# FPGA_NonIO.net
KiCad netlist of a schematic drawn in Altium Designer
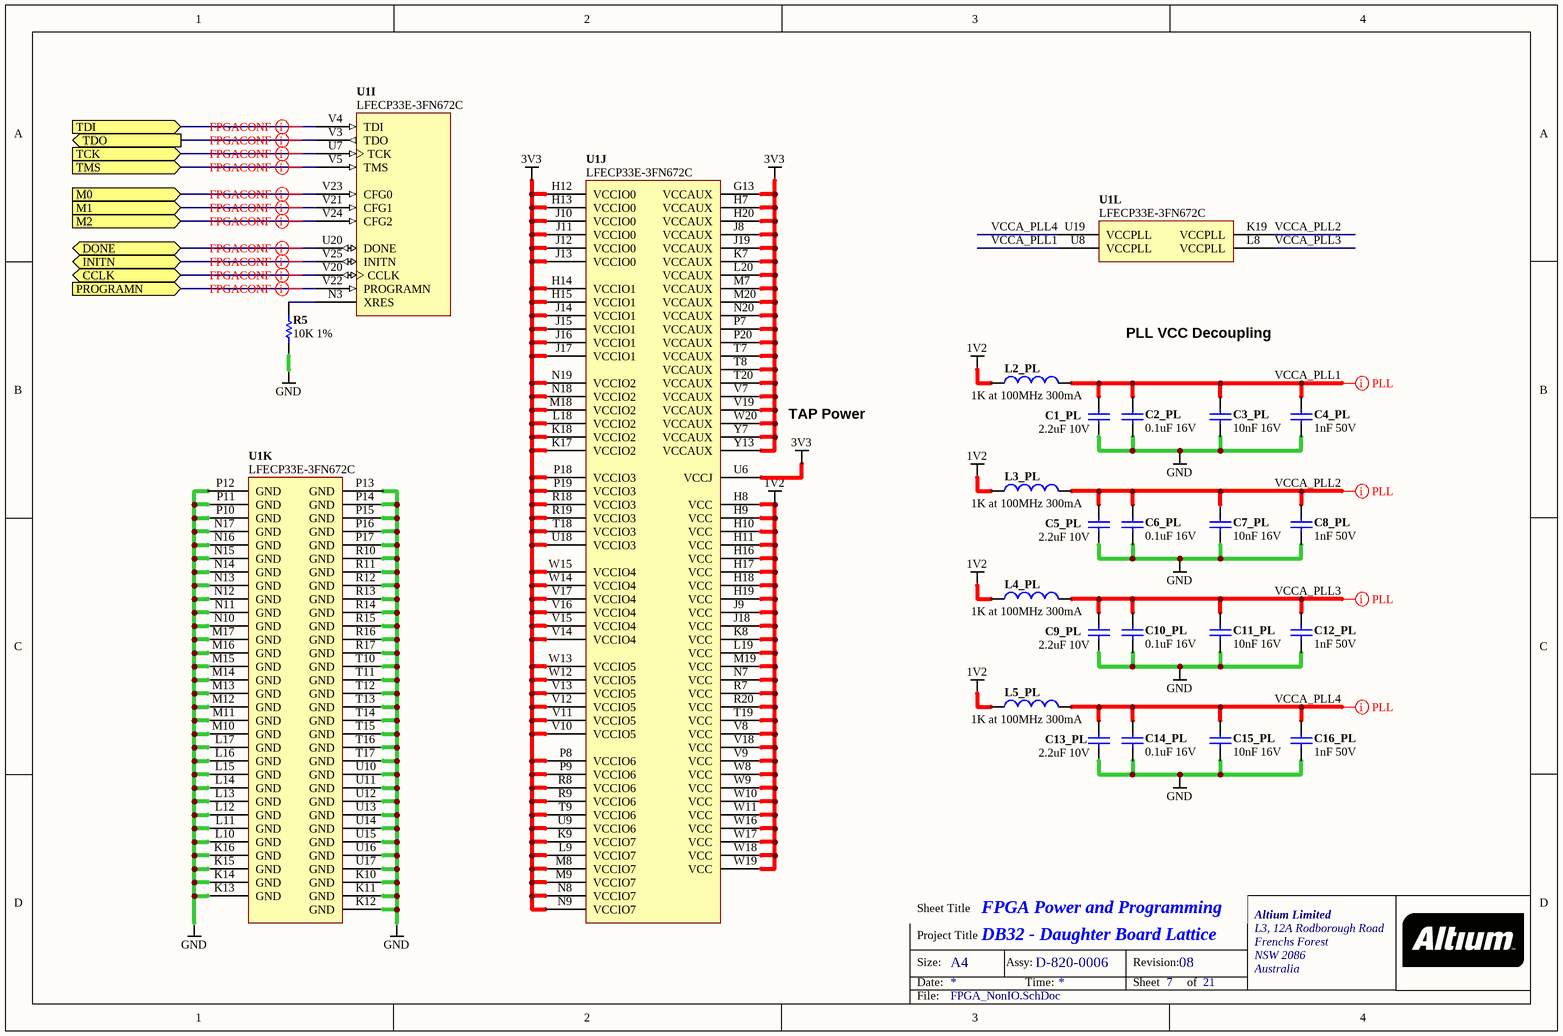
[diagram p0: FPGA_NonIO.SchDoc]

(export (version "E")
  (design (tool "Eeschema 10.0.6"))
  (components
    (comp (ref "C1_PL")
      (value "2.2uF 10V")
      (footprint "CAPC1608-STAR")
      (description "Capacitor, Ceramic, 2.2uF 10% 10V 0603 (1608) X5R")
      (fields (field (name "TOLERANCE") "10 %"))
      (libsource (lib "AltiumDesignLibrary") (part "CAP-NP"))
    )
    (comp (ref "C2_PL")
      (value "0.1uF 16V")
      (footprint "CAPC1005-STAR")
      (description "Capacitor, Ceramic, 0.1uF 10% 16V 0402 (1005) X7R")
      (fields (field (name "TOLERANCE") "10 %"))
      (libsource (lib "AltiumDesignLibrary") (part "CAP-NP"))
    )
    (comp (ref "C3_PL")
      (value "10nF 16V")
      (footprint "CAPC1005-STAR")
      (description "Capacitor, Ceramic, 10nF 10% 16V 0402 (1005) X7R")
      (fields (field (name "TOLERANCE") "10 %"))
      (libsource (lib "AltiumDesignLibrary") (part "CAP-NP"))
    )
    (comp (ref "C4_PL")
      (value "1nF 50V")
      (footprint "CAPC1005-STAR")
      (description "Capacitor, Ceramic, 1nF 10% 50V 0402 (1005) X7R")
      (fields (field (name "TOLERANCE") "10 %"))
      (libsource (lib "AltiumDesignLibrary") (part "CAP-NP"))
    )
    (comp (ref "C5_PL")
      (value "2.2uF 10V")
      (footprint "CAPC1608-STAR")
      (description "Capacitor, Ceramic, 2.2uF 10% 10V 0603 (1608) X5R")
      (fields (field (name "TOLERANCE") "10 %"))
      (libsource (lib "AltiumDesignLibrary") (part "CAP-NP"))
    )
    (comp (ref "C6_PL")
      (value "0.1uF 16V")
      (footprint "CAPC1005-STAR")
      (description "Capacitor, Ceramic, 0.1uF 10% 16V 0402 (1005) X7R")
      (fields (field (name "TOLERANCE") "10 %"))
      (libsource (lib "AltiumDesignLibrary") (part "CAP-NP"))
    )
    (comp (ref "C7_PL")
      (value "10nF 16V")
      (footprint "CAPC1005-STAR")
      (description "Capacitor, Ceramic, 10nF 10% 16V 0402 (1005) X7R")
      (fields (field (name "TOLERANCE") "10 %"))
      (libsource (lib "AltiumDesignLibrary") (part "CAP-NP"))
    )
    (comp (ref "C8_PL")
      (value "1nF 50V")
      (footprint "CAPC1005-STAR")
      (description "Capacitor, Ceramic, 1nF 10% 50V 0402 (1005) X7R")
      (fields (field (name "TOLERANCE") "10 %"))
      (libsource (lib "AltiumDesignLibrary") (part "CAP-NP"))
    )
    (comp (ref "C9_PL")
      (value "2.2uF 10V")
      (footprint "CAPC1608-STAR")
      (description "Capacitor, Ceramic, 2.2uF 10% 10V 0603 (1608) X5R")
      (fields (field (name "TOLERANCE") "10 %"))
      (libsource (lib "AltiumDesignLibrary") (part "CAP-NP"))
    )
    (comp (ref "C10_PL")
      (value "0.1uF 16V")
      (footprint "CAPC1005-STAR")
      (description "Capacitor, Ceramic, 0.1uF 10% 16V 0402 (1005) X7R")
      (fields (field (name "TOLERANCE") "10 %"))
      (libsource (lib "AltiumDesignLibrary") (part "CAP-NP"))
    )
    (comp (ref "C11_PL")
      (value "10nF 16V")
      (footprint "CAPC1005-STAR")
      (description "Capacitor, Ceramic, 10nF 10% 16V 0402 (1005) X7R")
      (fields (field (name "TOLERANCE") "10 %"))
      (libsource (lib "AltiumDesignLibrary") (part "CAP-NP"))
    )
    (comp (ref "C12_PL")
      (value "1nF 50V")
      (footprint "CAPC1005-STAR")
      (description "Capacitor, Ceramic, 1nF 10% 50V 0402 (1005) X7R")
      (fields (field (name "TOLERANCE") "10 %"))
      (libsource (lib "AltiumDesignLibrary") (part "CAP-NP"))
    )
    (comp (ref "C13_PL")
      (value "2.2uF 10V")
      (footprint "CAPC1608-STAR")
      (description "Capacitor, Ceramic, 2.2uF 10% 10V 0603 (1608) X5R")
      (fields (field (name "TOLERANCE") "10 %"))
      (libsource (lib "AltiumDesignLibrary") (part "CAP-NP"))
    )
    (comp (ref "C14_PL")
      (value "0.1uF 16V")
      (footprint "CAPC1005-STAR")
      (description "Capacitor, Ceramic, 0.1uF 10% 16V 0402 (1005) X7R")
      (fields (field (name "TOLERANCE") "10 %"))
      (libsource (lib "AltiumDesignLibrary") (part "CAP-NP"))
    )
    (comp (ref "C15_PL")
      (value "10nF 16V")
      (footprint "CAPC1005-STAR")
      (description "Capacitor, Ceramic, 10nF 10% 16V 0402 (1005) X7R")
      (fields (field (name "TOLERANCE") "10 %"))
      (libsource (lib "AltiumDesignLibrary") (part "CAP-NP"))
    )
    (comp (ref "C16_PL")
      (value "1nF 50V")
      (footprint "CAPC1005-STAR")
      (description "Capacitor, Ceramic, 1nF 10% 50V 0402 (1005) X7R")
      (fields (field (name "TOLERANCE") "10 %"))
      (libsource (lib "AltiumDesignLibrary") (part "CAP-NP"))
    )
    (comp (ref "L2_PL")
      (value "1K at 100MHz 300mA")
      (footprint "INDC2012-STAR")
      (description "Inductor, Ferrite Bead 1K@100MHz 300mA 0805 (2012) BMB2A1000LN2")
      (libsource (lib "AltiumDesignLibrary") (part "IND-FER"))
    )
    (comp (ref "L3_PL")
      (value "1K at 100MHz 300mA")
      (footprint "INDC2012-STAR")
      (description "Inductor, Ferrite Bead 1K@100MHz 300mA 0805 (2012) BMB2A1000LN2")
      (libsource (lib "AltiumDesignLibrary") (part "IND-FER"))
    )
    (comp (ref "L4_PL")
      (value "1K at 100MHz 300mA")
      (footprint "INDC2012-STAR")
      (description "Inductor, Ferrite Bead 1K@100MHz 300mA 0805 (2012) BMB2A1000LN2")
      (libsource (lib "AltiumDesignLibrary") (part "IND-FER"))
    )
    (comp (ref "L5_PL")
      (value "1K at 100MHz 300mA")
      (footprint "INDC2012-STAR")
      (description "Inductor, Ferrite Bead 1K@100MHz 300mA 0805 (2012) BMB2A1000LN2")
      (libsource (lib "AltiumDesignLibrary") (part "IND-FER"))
    )
    (comp (ref "R5")
      (value "10K 1%")
      (footprint "RESC1005-STAR")
      (description "Resistor, 10K 1% 0402 (1005)")
      (fields (field (name "TOLERANCE") "1 %"))
      (libsource (lib "AltiumDesignLibrary") (part "RES"))
    )
    (comp (ref "U1")
      (value "LFECP33E-3FN672C")
      (footprint "BGA100P26X26-672")
      (description "FPGA, Lattice ECP-35 FN672")
      (libsource (lib "AltiumDesignLibrary") (part "LFECP33E-3FN672C"))
    )
  )
  (nets
    (net (code "1") (name "/CCLK") (class "Default")
      (node (ref "U1") (pin "V20") (pinfunction "CCLK_V20") (pintype "bidirectional"))
    )
    (net (code "2") (name "/DONE") (class "Default")
      (node (ref "U1") (pin "U20") (pinfunction "DONE_U20") (pintype "bidirectional"))
    )
    (net (code "3") (name "/INITN") (class "Default")
      (node (ref "U1") (pin "V25") (pinfunction "INITN_V25") (pintype "bidirectional"))
    )
    (net (code "4") (name "/M0") (class "Default")
      (node (ref "U1") (pin "V23") (pinfunction "CFG0_V23") (pintype "input"))
    )
    (net (code "5") (name "/M1") (class "Default")
      (node (ref "U1") (pin "V21") (pinfunction "CFG1_V21") (pintype "input"))
    )
    (net (code "6") (name "/M2") (class "Default")
      (node (ref "U1") (pin "V24") (pinfunction "CFG2_V24") (pintype "input"))
    )
    (net (code "7") (name "/PROGRAMN") (class "Default")
      (node (ref "U1") (pin "V22") (pinfunction "PROGRAMN_V22") (pintype "input"))
    )
    (net (code "8") (name "/TCK") (class "Default")
      (node (ref "U1") (pin "U7") (pinfunction "TCK_U7") (pintype "input"))
    )
    (net (code "9") (name "/TDI") (class "Default")
      (node (ref "U1") (pin "V4") (pinfunction "TDI_V4") (pintype "input"))
    )
    (net (code "10") (name "/TDO") (class "Default")
      (node (ref "U1") (pin "V3") (pinfunction "TDO_V3") (pintype "output"))
    )
    (net (code "11") (name "/TMS") (class "Default")
      (node (ref "U1") (pin "V5") (pinfunction "TMS_V5") (pintype "input"))
    )
    (net (code "12") (name "/VCCA_PLL1") (class "Default")
      (node (ref "C1_PL") (pin "1") (pinfunction "1_1") (pintype "passive"))
      (node (ref "C2_PL") (pin "1") (pinfunction "1_1") (pintype "passive"))
      (node (ref "C3_PL") (pin "1") (pinfunction "1_1") (pintype "passive"))
      (node (ref "C4_PL") (pin "1") (pinfunction "1_1") (pintype "passive"))
      (node (ref "L2_PL") (pin "2") (pinfunction "2_2") (pintype "passive"))
      (node (ref "U1") (pin "U8") (pinfunction "VCCPLL_U8") (pintype "power_in"))
    )
    (net (code "13") (name "/VCCA_PLL2") (class "Default")
      (node (ref "C5_PL") (pin "1") (pinfunction "1_1") (pintype "passive"))
      (node (ref "C6_PL") (pin "1") (pinfunction "1_1") (pintype "passive"))
      (node (ref "C7_PL") (pin "1") (pinfunction "1_1") (pintype "passive"))
      (node (ref "C8_PL") (pin "1") (pinfunction "1_1") (pintype "passive"))
      (node (ref "L3_PL") (pin "2") (pinfunction "2_2") (pintype "passive"))
      (node (ref "U1") (pin "K19") (pinfunction "VCCPLL_K19") (pintype "power_in"))
    )
    (net (code "14") (name "/VCCA_PLL3") (class "Default")
      (node (ref "C10_PL") (pin "1") (pinfunction "1_1") (pintype "passive"))
      (node (ref "C11_PL") (pin "1") (pinfunction "1_1") (pintype "passive"))
      (node (ref "C12_PL") (pin "1") (pinfunction "1_1") (pintype "passive"))
      (node (ref "C9_PL") (pin "1") (pinfunction "1_1") (pintype "passive"))
      (node (ref "L4_PL") (pin "2") (pinfunction "2_2") (pintype "passive"))
      (node (ref "U1") (pin "L8") (pinfunction "VCCPLL_L8") (pintype "power_in"))
    )
    (net (code "15") (name "/VCCA_PLL4") (class "Default")
      (node (ref "C13_PL") (pin "1") (pinfunction "1_1") (pintype "passive"))
      (node (ref "C14_PL") (pin "1") (pinfunction "1_1") (pintype "passive"))
      (node (ref "C15_PL") (pin "1") (pinfunction "1_1") (pintype "passive"))
      (node (ref "C16_PL") (pin "1") (pinfunction "1_1") (pintype "passive"))
      (node (ref "L5_PL") (pin "2") (pinfunction "2_2") (pintype "passive"))
      (node (ref "U1") (pin "U19") (pinfunction "VCCPLL_U19") (pintype "power_in"))
    )
    (net (code "16") (name "1V2") (class "Default")
      (node (ref "L2_PL") (pin "1") (pinfunction "1_1") (pintype "passive"))
      (node (ref "L3_PL") (pin "1") (pinfunction "1_1") (pintype "passive"))
      (node (ref "L4_PL") (pin "1") (pinfunction "1_1") (pintype "passive"))
      (node (ref "L5_PL") (pin "1") (pinfunction "1_1") (pintype "passive"))
      (node (ref "U1") (pin "H10") (pinfunction "VCC_H10") (pintype "power_in"))
      (node (ref "U1") (pin "H11") (pinfunction "VCC_H11") (pintype "power_in"))
      (node (ref "U1") (pin "H16") (pinfunction "VCC_H16") (pintype "power_in"))
      (node (ref "U1") (pin "H17") (pinfunction "VCC_H17") (pintype "power_in"))
      (node (ref "U1") (pin "H18") (pinfunction "VCC_H18") (pintype "power_in"))
      (node (ref "U1") (pin "H19") (pinfunction "VCC_H19") (pintype "power_in"))
      (node (ref "U1") (pin "H8") (pinfunction "VCC_H8") (pintype "power_in"))
      (node (ref "U1") (pin "H9") (pinfunction "VCC_H9") (pintype "power_in"))
      (node (ref "U1") (pin "J18") (pinfunction "VCC_J18") (pintype "power_in"))
      (node (ref "U1") (pin "J9") (pinfunction "VCC_J9") (pintype "power_in"))
      (node (ref "U1") (pin "K8") (pinfunction "VCC_K8") (pintype "power_in"))
      (node (ref "U1") (pin "L19") (pinfunction "VCC_L19") (pintype "power_in"))
      (node (ref "U1") (pin "M19") (pinfunction "VCC_M19") (pintype "power_in"))
      (node (ref "U1") (pin "N7") (pinfunction "VCC_N7") (pintype "power_in"))
      (node (ref "U1") (pin "R20") (pinfunction "VCC_R20") (pintype "power_in"))
      (node (ref "U1") (pin "R7") (pinfunction "VCC_R7") (pintype "power_in"))
      (node (ref "U1") (pin "T19") (pinfunction "VCC_T19") (pintype "power_in"))
      (node (ref "U1") (pin "V18") (pinfunction "VCC_V18") (pintype "power_in"))
      (node (ref "U1") (pin "V8") (pinfunction "VCC_V8") (pintype "power_in"))
      (node (ref "U1") (pin "V9") (pinfunction "VCC_V9") (pintype "power_in"))
      (node (ref "U1") (pin "W10") (pinfunction "VCC_W10") (pintype "power_in"))
      (node (ref "U1") (pin "W11") (pinfunction "VCC_W11") (pintype "power_in"))
      (node (ref "U1") (pin "W16") (pinfunction "VCC_W16") (pintype "power_in"))
      (node (ref "U1") (pin "W17") (pinfunction "VCC_W17") (pintype "power_in"))
      (node (ref "U1") (pin "W18") (pinfunction "VCC_W18") (pintype "power_in"))
      (node (ref "U1") (pin "W19") (pinfunction "VCC_W19") (pintype "power_in"))
      (node (ref "U1") (pin "W8") (pinfunction "VCC_W8") (pintype "power_in"))
      (node (ref "U1") (pin "W9") (pinfunction "VCC_W9") (pintype "power_in"))
    )
    (net (code "17") (name "3V3") (class "Default")
      (node (ref "U1") (pin "G13") (pinfunction "VCCAUX_G13") (pintype "power_in"))
      (node (ref "U1") (pin "H12") (pinfunction "VCCIO0_H12") (pintype "power_in"))
      (node (ref "U1") (pin "H13") (pinfunction "VCCIO0_H13") (pintype "power_in"))
      (node (ref "U1") (pin "H14") (pinfunction "VCCIO1_H14") (pintype "power_in"))
      (node (ref "U1") (pin "H15") (pinfunction "VCCIO1_H15") (pintype "power_in"))
      (node (ref "U1") (pin "H20") (pinfunction "VCCAUX_H20") (pintype "power_in"))
      (node (ref "U1") (pin "H7") (pinfunction "VCCAUX_H7") (pintype "power_in"))
      (node (ref "U1") (pin "J10") (pinfunction "VCCIO0_J10") (pintype "power_in"))
      (node (ref "U1") (pin "J11") (pinfunction "VCCIO0_J11") (pintype "power_in"))
      (node (ref "U1") (pin "J12") (pinfunction "VCCIO0_J12") (pintype "power_in"))
      (node (ref "U1") (pin "J13") (pinfunction "VCCIO0_J13") (pintype "power_in"))
      (node (ref "U1") (pin "J14") (pinfunction "VCCIO1_J14") (pintype "power_in"))
      (node (ref "U1") (pin "J15") (pinfunction "VCCIO1_J15") (pintype "power_in"))
      (node (ref "U1") (pin "J16") (pinfunction "VCCIO1_J16") (pintype "power_in"))
      (node (ref "U1") (pin "J17") (pinfunction "VCCIO1_J17") (pintype "power_in"))
      (node (ref "U1") (pin "J19") (pinfunction "VCCAUX_J19") (pintype "power_in"))
      (node (ref "U1") (pin "J8") (pinfunction "VCCAUX_J8") (pintype "power_in"))
      (node (ref "U1") (pin "K17") (pinfunction "VCCIO2_K17") (pintype "power_in"))
      (node (ref "U1") (pin "K18") (pinfunction "VCCIO2_K18") (pintype "power_in"))
      (node (ref "U1") (pin "K7") (pinfunction "VCCAUX_K7") (pintype "power_in"))
      (node (ref "U1") (pin "K9") (pinfunction "VCCIO7_K9") (pintype "power_in"))
      (node (ref "U1") (pin "L18") (pinfunction "VCCIO2_L18") (pintype "power_in"))
      (node (ref "U1") (pin "L20") (pinfunction "VCCAUX_L20") (pintype "power_in"))
      (node (ref "U1") (pin "L9") (pinfunction "VCCIO7_L9") (pintype "power_in"))
      (node (ref "U1") (pin "M18") (pinfunction "VCCIO2_M18") (pintype "power_in"))
      (node (ref "U1") (pin "M20") (pinfunction "VCCAUX_M20") (pintype "power_in"))
      (node (ref "U1") (pin "M7") (pinfunction "VCCAUX_M7") (pintype "power_in"))
      (node (ref "U1") (pin "M8") (pinfunction "VCCIO7_M8") (pintype "power_in"))
      (node (ref "U1") (pin "M9") (pinfunction "VCCIO7_M9") (pintype "power_in"))
      (node (ref "U1") (pin "N18") (pinfunction "VCCIO2_N18") (pintype "power_in"))
      (node (ref "U1") (pin "N19") (pinfunction "VCCIO2_N19") (pintype "power_in"))
      (node (ref "U1") (pin "N20") (pinfunction "VCCAUX_N20") (pintype "power_in"))
      (node (ref "U1") (pin "N8") (pinfunction "VCCIO7_N8") (pintype "power_in"))
      (node (ref "U1") (pin "N9") (pinfunction "VCCIO7_N9") (pintype "power_in"))
      (node (ref "U1") (pin "P18") (pinfunction "VCCIO3_P18") (pintype "power_in"))
      (node (ref "U1") (pin "P19") (pinfunction "VCCIO3_P19") (pintype "power_in"))
      (node (ref "U1") (pin "P20") (pinfunction "VCCAUX_P20") (pintype "power_in"))
      (node (ref "U1") (pin "P7") (pinfunction "VCCAUX_P7") (pintype "power_in"))
      (node (ref "U1") (pin "P8") (pinfunction "VCCIO6_P8") (pintype "power_in"))
      (node (ref "U1") (pin "P9") (pinfunction "VCCIO6_P9") (pintype "power_in"))
      (node (ref "U1") (pin "R18") (pinfunction "VCCIO3_R18") (pintype "power_in"))
      (node (ref "U1") (pin "R19") (pinfunction "VCCIO3_R19") (pintype "power_in"))
      (node (ref "U1") (pin "R8") (pinfunction "VCCIO6_R8") (pintype "power_in"))
      (node (ref "U1") (pin "R9") (pinfunction "VCCIO6_R9") (pintype "power_in"))
      (node (ref "U1") (pin "T18") (pinfunction "VCCIO3_T18") (pintype "power_in"))
      (node (ref "U1") (pin "T20") (pinfunction "VCCAUX_T20") (pintype "power_in"))
      (node (ref "U1") (pin "T7") (pinfunction "VCCAUX_T7") (pintype "power_in"))
      (node (ref "U1") (pin "T8") (pinfunction "VCCAUX_T8") (pintype "power_in"))
      (node (ref "U1") (pin "T9") (pinfunction "VCCIO6_T9") (pintype "power_in"))
      (node (ref "U1") (pin "U18") (pinfunction "VCCIO3_U18") (pintype "power_in"))
      (node (ref "U1") (pin "U6") (pinfunction "VCCJ_U6") (pintype "power_in"))
      (node (ref "U1") (pin "U9") (pinfunction "VCCIO6_U9") (pintype "power_in"))
      (node (ref "U1") (pin "V10") (pinfunction "VCCIO5_V10") (pintype "power_in"))
      (node (ref "U1") (pin "V11") (pinfunction "VCCIO5_V11") (pintype "power_in"))
      (node (ref "U1") (pin "V12") (pinfunction "VCCIO5_V12") (pintype "power_in"))
      (node (ref "U1") (pin "V13") (pinfunction "VCCIO5_V13") (pintype "power_in"))
      (node (ref "U1") (pin "V14") (pinfunction "VCCIO4_V14") (pintype "power_in"))
      (node (ref "U1") (pin "V15") (pinfunction "VCCIO4_V15") (pintype "power_in"))
      (node (ref "U1") (pin "V16") (pinfunction "VCCIO4_V16") (pintype "power_in"))
      (node (ref "U1") (pin "V17") (pinfunction "VCCIO4_V17") (pintype "power_in"))
      (node (ref "U1") (pin "V19") (pinfunction "VCCAUX_V19") (pintype "power_in"))
      (node (ref "U1") (pin "V7") (pinfunction "VCCAUX_V7") (pintype "power_in"))
      (node (ref "U1") (pin "W12") (pinfunction "VCCIO5_W12") (pintype "power_in"))
      (node (ref "U1") (pin "W13") (pinfunction "VCCIO5_W13") (pintype "power_in"))
      (node (ref "U1") (pin "W14") (pinfunction "VCCIO4_W14") (pintype "power_in"))
      (node (ref "U1") (pin "W15") (pinfunction "VCCIO4_W15") (pintype "power_in"))
      (node (ref "U1") (pin "W20") (pinfunction "VCCAUX_W20") (pintype "power_in"))
      (node (ref "U1") (pin "Y13") (pinfunction "VCCAUX_Y13") (pintype "power_in"))
      (node (ref "U1") (pin "Y7") (pinfunction "VCCAUX_Y7") (pintype "power_in"))
    )
    (net (code "18") (name "GND") (class "Default")
      (node (ref "C10_PL") (pin "2") (pinfunction "2_2") (pintype "passive"))
      (node (ref "C11_PL") (pin "2") (pinfunction "2_2") (pintype "passive"))
      (node (ref "C12_PL") (pin "2") (pinfunction "2_2") (pintype "passive"))
      (node (ref "C13_PL") (pin "2") (pinfunction "2_2") (pintype "passive"))
      (node (ref "C14_PL") (pin "2") (pinfunction "2_2") (pintype "passive"))
      (node (ref "C15_PL") (pin "2") (pinfunction "2_2") (pintype "passive"))
      (node (ref "C16_PL") (pin "2") (pinfunction "2_2") (pintype "passive"))
      (node (ref "C1_PL") (pin "2") (pinfunction "2_2") (pintype "passive"))
      (node (ref "C2_PL") (pin "2") (pinfunction "2_2") (pintype "passive"))
      (node (ref "C3_PL") (pin "2") (pinfunction "2_2") (pintype "passive"))
      (node (ref "C4_PL") (pin "2") (pinfunction "2_2") (pintype "passive"))
      (node (ref "C5_PL") (pin "2") (pinfunction "2_2") (pintype "passive"))
      (node (ref "C6_PL") (pin "2") (pinfunction "2_2") (pintype "passive"))
      (node (ref "C7_PL") (pin "2") (pinfunction "2_2") (pintype "passive"))
      (node (ref "C8_PL") (pin "2") (pinfunction "2_2") (pintype "passive"))
      (node (ref "C9_PL") (pin "2") (pinfunction "2_2") (pintype "passive"))
      (node (ref "R5") (pin "2") (pinfunction "2_2") (pintype "passive"))
      (node (ref "U1") (pin "K10") (pinfunction "GND_K10") (pintype "power_in"))
      (node (ref "U1") (pin "K11") (pinfunction "GND_K11") (pintype "power_in"))
      (node (ref "U1") (pin "K12") (pinfunction "GND_K12") (pintype "power_in"))
      (node (ref "U1") (pin "K13") (pinfunction "GND_K13") (pintype "power_in"))
      (node (ref "U1") (pin "K14") (pinfunction "GND_K14") (pintype "power_in"))
      (node (ref "U1") (pin "K15") (pinfunction "GND_K15") (pintype "power_in"))
      (node (ref "U1") (pin "K16") (pinfunction "GND_K16") (pintype "power_in"))
      (node (ref "U1") (pin "L10") (pinfunction "GND_L10") (pintype "power_in"))
      (node (ref "U1") (pin "L11") (pinfunction "GND_L11") (pintype "power_in"))
      (node (ref "U1") (pin "L12") (pinfunction "GND_L12") (pintype "power_in"))
      (node (ref "U1") (pin "L13") (pinfunction "GND_L13") (pintype "power_in"))
      (node (ref "U1") (pin "L14") (pinfunction "GND_L14") (pintype "power_in"))
      (node (ref "U1") (pin "L15") (pinfunction "GND_L15") (pintype "power_in"))
      (node (ref "U1") (pin "L16") (pinfunction "GND_L16") (pintype "power_in"))
      (node (ref "U1") (pin "L17") (pinfunction "GND_L17") (pintype "power_in"))
      (node (ref "U1") (pin "M10") (pinfunction "GND_M10") (pintype "power_in"))
      (node (ref "U1") (pin "M11") (pinfunction "GND_M11") (pintype "power_in"))
      (node (ref "U1") (pin "M12") (pinfunction "GND_M12") (pintype "power_in"))
      (node (ref "U1") (pin "M13") (pinfunction "GND_M13") (pintype "power_in"))
      (node (ref "U1") (pin "M14") (pinfunction "GND_M14") (pintype "power_in"))
      (node (ref "U1") (pin "M15") (pinfunction "GND_M15") (pintype "power_in"))
      (node (ref "U1") (pin "M16") (pinfunction "GND_M16") (pintype "power_in"))
      (node (ref "U1") (pin "M17") (pinfunction "GND_M17") (pintype "power_in"))
      (node (ref "U1") (pin "N10") (pinfunction "GND_N10") (pintype "power_in"))
      (node (ref "U1") (pin "N11") (pinfunction "GND_N11") (pintype "power_in"))
      (node (ref "U1") (pin "N12") (pinfunction "GND_N12") (pintype "power_in"))
      (node (ref "U1") (pin "N13") (pinfunction "GND_N13") (pintype "power_in"))
      (node (ref "U1") (pin "N14") (pinfunction "GND_N14") (pintype "power_in"))
      (node (ref "U1") (pin "N15") (pinfunction "GND_N15") (pintype "power_in"))
      (node (ref "U1") (pin "N16") (pinfunction "GND_N16") (pintype "power_in"))
      (node (ref "U1") (pin "N17") (pinfunction "GND_N17") (pintype "power_in"))
      (node (ref "U1") (pin "P10") (pinfunction "GND_P10") (pintype "power_in"))
      (node (ref "U1") (pin "P11") (pinfunction "GND_P11") (pintype "power_in"))
      (node (ref "U1") (pin "P12") (pinfunction "GND_P12") (pintype "power_in"))
      (node (ref "U1") (pin "P13") (pinfunction "GND_P13") (pintype "power_in"))
      (node (ref "U1") (pin "P14") (pinfunction "GND_P14") (pintype "power_in"))
      (node (ref "U1") (pin "P15") (pinfunction "GND_P15") (pintype "power_in"))
      (node (ref "U1") (pin "P16") (pinfunction "GND_P16") (pintype "power_in"))
      (node (ref "U1") (pin "P17") (pinfunction "GND_P17") (pintype "power_in"))
      (node (ref "U1") (pin "R10") (pinfunction "GND_R10") (pintype "power_in"))
      (node (ref "U1") (pin "R11") (pinfunction "GND_R11") (pintype "power_in"))
      (node (ref "U1") (pin "R12") (pinfunction "GND_R12") (pintype "power_in"))
      (node (ref "U1") (pin "R13") (pinfunction "GND_R13") (pintype "power_in"))
      (node (ref "U1") (pin "R14") (pinfunction "GND_R14") (pintype "power_in"))
      (node (ref "U1") (pin "R15") (pinfunction "GND_R15") (pintype "power_in"))
      (node (ref "U1") (pin "R16") (pinfunction "GND_R16") (pintype "power_in"))
      (node (ref "U1") (pin "R17") (pinfunction "GND_R17") (pintype "power_in"))
      (node (ref "U1") (pin "T10") (pinfunction "GND_T10") (pintype "power_in"))
      (node (ref "U1") (pin "T11") (pinfunction "GND_T11") (pintype "power_in"))
      (node (ref "U1") (pin "T12") (pinfunction "GND_T12") (pintype "power_in"))
      (node (ref "U1") (pin "T13") (pinfunction "GND_T13") (pintype "power_in"))
      (node (ref "U1") (pin "T14") (pinfunction "GND_T14") (pintype "power_in"))
      (node (ref "U1") (pin "T15") (pinfunction "GND_T15") (pintype "power_in"))
      (node (ref "U1") (pin "T16") (pinfunction "GND_T16") (pintype "power_in"))
      (node (ref "U1") (pin "T17") (pinfunction "GND_T17") (pintype "power_in"))
      (node (ref "U1") (pin "U10") (pinfunction "GND_U10") (pintype "power_in"))
      (node (ref "U1") (pin "U11") (pinfunction "GND_U11") (pintype "power_in"))
      (node (ref "U1") (pin "U12") (pinfunction "GND_U12") (pintype "power_in"))
      (node (ref "U1") (pin "U13") (pinfunction "GND_U13") (pintype "power_in"))
      (node (ref "U1") (pin "U14") (pinfunction "GND_U14") (pintype "power_in"))
      (node (ref "U1") (pin "U15") (pinfunction "GND_U15") (pintype "power_in"))
      (node (ref "U1") (pin "U16") (pinfunction "GND_U16") (pintype "power_in"))
      (node (ref "U1") (pin "U17") (pinfunction "GND_U17") (pintype "power_in"))
    )
    (net (code "19") (name "Net-(U1I-XRES)") (class "Default")
      (node (ref "R5") (pin "1") (pinfunction "1_1") (pintype "passive"))
      (node (ref "U1") (pin "N3") (pinfunction "XRES_N3") (pintype "passive"))
    )
  )
)
